# IO__MCP23017_20240819.net
KiCad netlist of a schematic drawn in Altium Designer
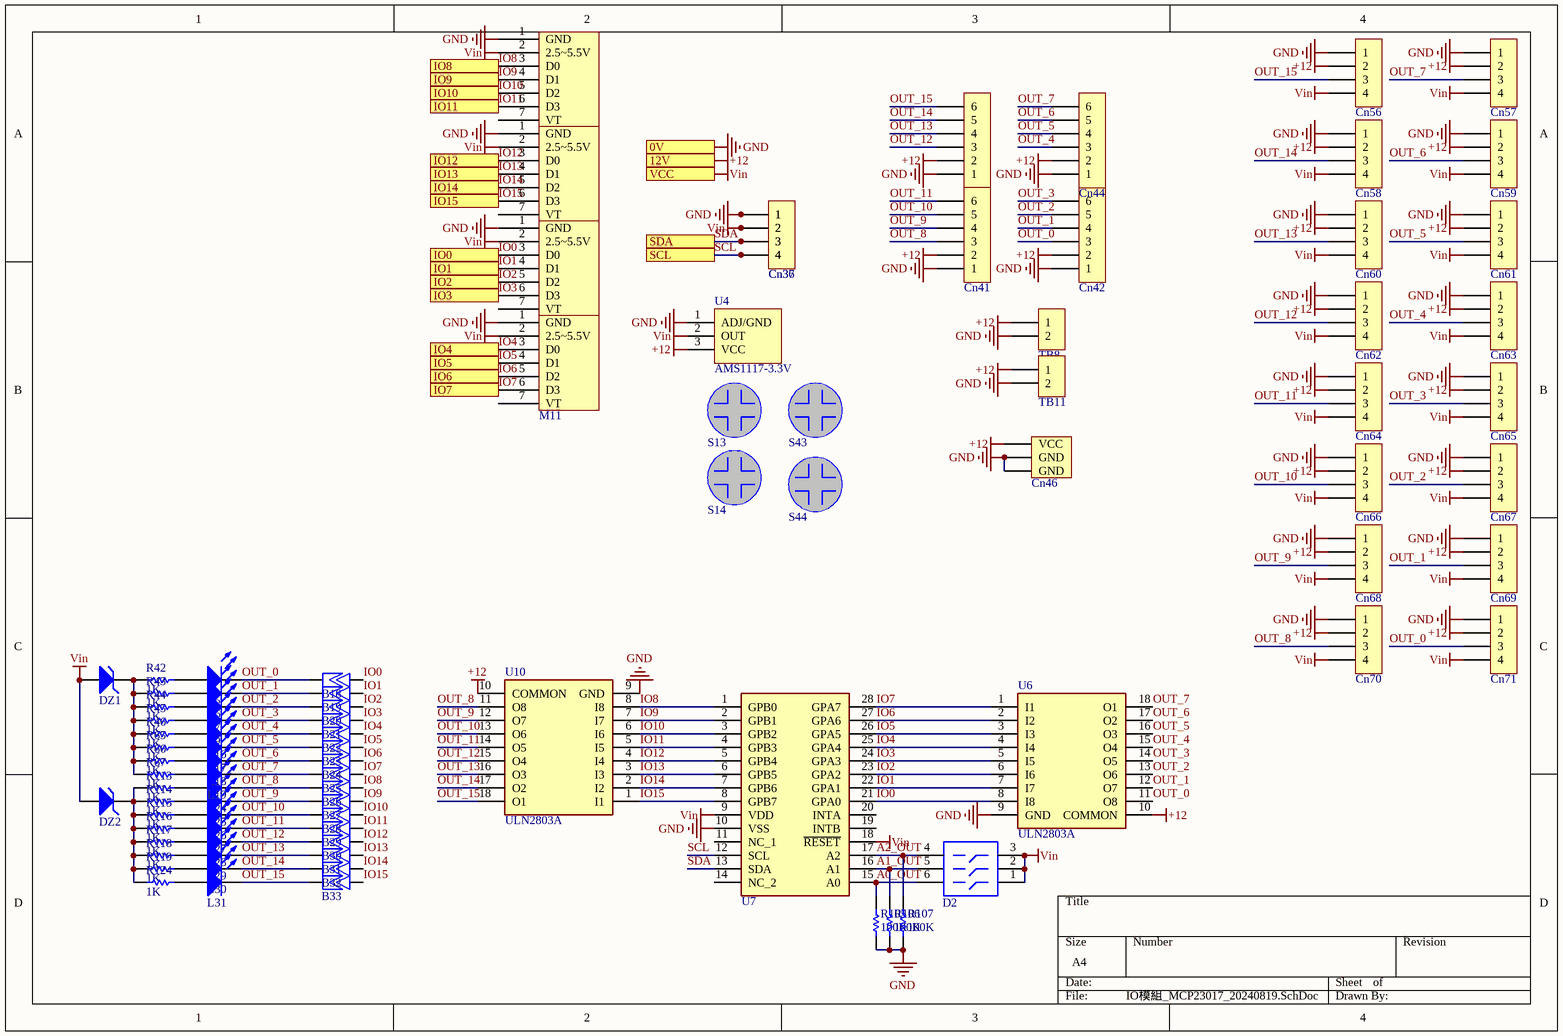
[diagram p0: IO模組_MCP23017_20240819.SchDoc]

(export (version "E")
  (design (tool "Eeschema 10.0.6"))
  (components
    (comp (ref "B18")
      (value "短路")
      (footprint "BYPASS-0805")
      (description "短路焊點(如標註短路則需額外補錫使其短路)")
      (libsource (lib "MyLibray") (part "Bypass"))
    )
    (comp (ref "B19")
      (value "短路")
      (footprint "BYPASS-0805")
      (description "短路焊點(如標註短路則需額外補錫使其短路)")
      (libsource (lib "MyLibray") (part "Bypass"))
    )
    (comp (ref "B20")
      (value "短路")
      (footprint "BYPASS-0805")
      (description "短路焊點(如標註短路則需額外補錫使其短路)")
      (libsource (lib "MyLibray") (part "Bypass"))
    )
    (comp (ref "B21")
      (value "短路")
      (footprint "BYPASS-0805")
      (description "短路焊點(如標註短路則需額外補錫使其短路)")
      (libsource (lib "MyLibray") (part "Bypass"))
    )
    (comp (ref "B22")
      (value "短路")
      (footprint "BYPASS-0805")
      (description "短路焊點(如標註短路則需額外補錫使其短路)")
      (libsource (lib "MyLibray") (part "Bypass"))
    )
    (comp (ref "B23")
      (value "短路")
      (footprint "BYPASS-0805")
      (description "短路焊點(如標註短路則需額外補錫使其短路)")
      (libsource (lib "MyLibray") (part "Bypass"))
    )
    (comp (ref "B24")
      (value "短路")
      (footprint "BYPASS-0805")
      (description "短路焊點(如標註短路則需額外補錫使其短路)")
      (libsource (lib "MyLibray") (part "Bypass"))
    )
    (comp (ref "B25")
      (value "短路")
      (footprint "BYPASS-0805")
      (description "短路焊點(如標註短路則需額外補錫使其短路)")
      (libsource (lib "MyLibray") (part "Bypass"))
    )
    (comp (ref "B26")
      (value "短路")
      (footprint "BYPASS-0805")
      (description "短路焊點(如標註短路則需額外補錫使其短路)")
      (libsource (lib "MyLibray") (part "Bypass"))
    )
    (comp (ref "B27")
      (value "短路")
      (footprint "BYPASS-0805")
      (description "短路焊點(如標註短路則需額外補錫使其短路)")
      (libsource (lib "MyLibray") (part "Bypass"))
    )
    (comp (ref "B28")
      (value "短路")
      (footprint "BYPASS-0805")
      (description "短路焊點(如標註短路則需額外補錫使其短路)")
      (libsource (lib "MyLibray") (part "Bypass"))
    )
    (comp (ref "B29")
      (value "短路")
      (footprint "BYPASS-0805")
      (description "短路焊點(如標註短路則需額外補錫使其短路)")
      (libsource (lib "MyLibray") (part "Bypass"))
    )
    (comp (ref "B30")
      (value "短路")
      (footprint "BYPASS-0805")
      (description "短路焊點(如標註短路則需額外補錫使其短路)")
      (libsource (lib "MyLibray") (part "Bypass"))
    )
    (comp (ref "B31")
      (value "短路")
      (footprint "BYPASS-0805")
      (description "短路焊點(如標註短路則需額外補錫使其短路)")
      (libsource (lib "MyLibray") (part "Bypass"))
    )
    (comp (ref "B32")
      (value "短路")
      (footprint "BYPASS-0805")
      (description "短路焊點(如標註短路則需額外補錫使其短路)")
      (libsource (lib "MyLibray") (part "Bypass"))
    )
    (comp (ref "B33")
      (value "短路")
      (footprint "BYPASS-0805")
      (description "短路焊點(如標註短路則需額外補錫使其短路)")
      (libsource (lib "MyLibray") (part "Bypass"))
    )
    (comp (ref "Cn36")
      (value "KF2510")
      (footprint "Connector_KF2510-4A")
      (description "接線端子")
      (libsource (lib "MyLibray") (part "Contact(4P)"))
    )
    (comp (ref "Cn37")
      (value "KF2510")
      (footprint "Connector_KF2510-4A")
      (description "接線端子")
      (libsource (lib "MyLibray") (part "Contact(4P)"))
    )
    (comp (ref "Cn39")
      (value "KF2510-6")
      (footprint "Connector_KF2510-6W")
      (description "接線端子")
      (libsource (lib "MyLibray") (part "Contact(6P)"))
    )
    (comp (ref "Cn41")
      (value "KF2510-6")
      (footprint "Connector_KF2510-6W")
      (description "接線端子")
      (libsource (lib "MyLibray") (part "Contact(6P)"))
    )
    (comp (ref "Cn42")
      (value "KF2510-6")
      (footprint "Connector_KF2510-6W")
      (description "接線端子")
      (libsource (lib "MyLibray") (part "Contact(6P)"))
    )
    (comp (ref "Cn44")
      (value "KF2510-6")
      (footprint "Connector_KF2510-6W")
      (description "接線端子")
      (libsource (lib "MyLibray") (part "Contact(6P)"))
    )
    (comp (ref "Cn46")
      (value "KF2510-4")
      (footprint "Connector_DC-005")
      (description "接線端子")
      (libsource (lib "MyLibray") (part "Contact_DC"))
    )
    (comp (ref "Cn56")
      (value "KF2510")
      (footprint "Connector_KF2510-4A")
      (description "接線端子")
      (libsource (lib "MyLibray") (part "Contact(4P)"))
    )
    (comp (ref "Cn57")
      (value "KF2510")
      (footprint "Connector_KF2510-4A")
      (description "接線端子")
      (libsource (lib "MyLibray") (part "Contact(4P)"))
    )
    (comp (ref "Cn58")
      (value "KF2510")
      (footprint "Connector_KF2510-4A")
      (description "接線端子")
      (libsource (lib "MyLibray") (part "Contact(4P)"))
    )
    (comp (ref "Cn59")
      (value "KF2510")
      (footprint "Connector_KF2510-4A")
      (description "接線端子")
      (libsource (lib "MyLibray") (part "Contact(4P)"))
    )
    (comp (ref "Cn60")
      (value "KF2510")
      (footprint "Connector_KF2510-4A")
      (description "接線端子")
      (libsource (lib "MyLibray") (part "Contact(4P)"))
    )
    (comp (ref "Cn61")
      (value "KF2510")
      (footprint "Connector_KF2510-4A")
      (description "接線端子")
      (libsource (lib "MyLibray") (part "Contact(4P)"))
    )
    (comp (ref "Cn62")
      (value "KF2510")
      (footprint "Connector_KF2510-4A")
      (description "接線端子")
      (libsource (lib "MyLibray") (part "Contact(4P)"))
    )
    (comp (ref "Cn63")
      (value "KF2510")
      (footprint "Connector_KF2510-4A")
      (description "接線端子")
      (libsource (lib "MyLibray") (part "Contact(4P)"))
    )
    (comp (ref "Cn64")
      (value "KF2510")
      (footprint "Connector_KF2510-4A")
      (description "接線端子")
      (libsource (lib "MyLibray") (part "Contact(4P)"))
    )
    (comp (ref "Cn65")
      (value "KF2510")
      (footprint "Connector_KF2510-4A")
      (description "接線端子")
      (libsource (lib "MyLibray") (part "Contact(4P)"))
    )
    (comp (ref "Cn66")
      (value "KF2510")
      (footprint "Connector_KF2510-4A")
      (description "接線端子")
      (libsource (lib "MyLibray") (part "Contact(4P)"))
    )
    (comp (ref "Cn67")
      (value "KF2510")
      (footprint "Connector_KF2510-4A")
      (description "接線端子")
      (libsource (lib "MyLibray") (part "Contact(4P)"))
    )
    (comp (ref "Cn68")
      (value "KF2510")
      (footprint "Connector_KF2510-4A")
      (description "接線端子")
      (libsource (lib "MyLibray") (part "Contact(4P)"))
    )
    (comp (ref "Cn69")
      (value "KF2510")
      (footprint "Connector_KF2510-4A")
      (description "接線端子")
      (libsource (lib "MyLibray") (part "Contact(4P)"))
    )
    (comp (ref "Cn70")
      (value "KF2510")
      (footprint "Connector_KF2510-4A")
      (description "接線端子")
      (libsource (lib "MyLibray") (part "Contact(4P)"))
    )
    (comp (ref "Cn71")
      (value "KF2510")
      (footprint "Connector_KF2510-4A")
      (description "接線端子")
      (libsource (lib "MyLibray") (part "Contact(4P)"))
    )
    (comp (ref "D2")
      (value "KE 撥碼開關 1.27mm")
      (footprint "Switch_Dip-3")
      (description "開關_撥碼_3位")
      (libsource (lib "MyLibray") (part "Switch_Dip _3"))
    )
    (comp (ref "DZ1")
      (value "12V1")
      (footprint "Diode_1/4")
      (description "二極體_稽納")
      (libsource (lib "MyLibray") (part "Diode_Zener"))
    )
    (comp (ref "DZ2")
      (value "12V1")
      (footprint "Diode_1/4")
      (description "二極體_稽納")
      (libsource (lib "MyLibray") (part "Diode_Zener"))
    )
    (comp (ref "L5")
      (value "藍")
      (footprint "LED-1206")
      (description "LED")
      (libsource (lib "MyLibray") (part "LED"))
    )
    (comp (ref "L6")
      (value "藍")
      (footprint "LED-1206")
      (description "LED")
      (libsource (lib "MyLibray") (part "LED"))
    )
    (comp (ref "L7")
      (value "藍")
      (footprint "LED-1206")
      (description "LED")
      (libsource (lib "MyLibray") (part "LED"))
    )
    (comp (ref "L9")
      (value "藍")
      (footprint "LED-1206")
      (description "LED")
      (libsource (lib "MyLibray") (part "LED"))
    )
    (comp (ref "L16")
      (value "藍")
      (footprint "LED-1206")
      (description "LED")
      (libsource (lib "MyLibray") (part "LED"))
    )
    (comp (ref "L17")
      (value "藍")
      (footprint "LED-1206")
      (description "LED")
      (libsource (lib "MyLibray") (part "LED"))
    )
    (comp (ref "L18")
      (value "藍")
      (footprint "LED-1206")
      (description "LED")
      (libsource (lib "MyLibray") (part "LED"))
    )
    (comp (ref "L19")
      (value "藍")
      (footprint "LED-1206")
      (description "LED")
      (libsource (lib "MyLibray") (part "LED"))
    )
    (comp (ref "L24")
      (value "藍")
      (footprint "LED-1206")
      (description "LED")
      (libsource (lib "MyLibray") (part "LED"))
    )
    (comp (ref "L25")
      (value "藍")
      (footprint "LED-1206")
      (description "LED")
      (libsource (lib "MyLibray") (part "LED"))
    )
    (comp (ref "L26")
      (value "藍")
      (footprint "LED-1206")
      (description "LED")
      (libsource (lib "MyLibray") (part "LED"))
    )
    (comp (ref "L27")
      (value "藍")
      (footprint "LED-1206")
      (description "LED")
      (libsource (lib "MyLibray") (part "LED"))
    )
    (comp (ref "L28")
      (value "藍")
      (footprint "LED-1206")
      (description "LED")
      (libsource (lib "MyLibray") (part "LED"))
    )
    (comp (ref "L29")
      (value "藍")
      (footprint "LED-1206")
      (description "LED")
      (libsource (lib "MyLibray") (part "LED"))
    )
    (comp (ref "L30")
      (value "藍")
      (footprint "LED-1206")
      (description "LED")
      (libsource (lib "MyLibray") (part "LED"))
    )
    (comp (ref "L31")
      (value "藍")
      (footprint "LED-1206")
      (description "LED")
      (libsource (lib "MyLibray") (part "LED"))
    )
    (comp (ref "M8")
      (value "XR390")
      (footprint "XR390 Module")
      (description "遙控器模組")
      (libsource (lib "MyModule") (part "XR390"))
    )
    (comp (ref "M9")
      (value "XR390")
      (footprint "XR390 Module")
      (description "遙控器模組")
      (libsource (lib "MyModule") (part "XR390"))
    )
    (comp (ref "M10")
      (value "XR390")
      (footprint "XR390 Module")
      (description "遙控器模組")
      (libsource (lib "MyModule") (part "XR390"))
    )
    (comp (ref "M11")
      (value "XR390")
      (footprint "XR390 Module")
      (description "遙控器模組")
      (libsource (lib "MyModule") (part "XR390"))
    )
    (comp (ref "R42")
      (value "1K")
      (footprint "Res-1206")
      (description "電阻")
      (libsource (lib "MyLibray") (part "Res"))
    )
    (comp (ref "R43")
      (value "1K")
      (footprint "Res-1206")
      (description "電阻")
      (libsource (lib "MyLibray") (part "Res"))
    )
    (comp (ref "R44")
      (value "1K")
      (footprint "Res-1206")
      (description "電阻")
      (libsource (lib "MyLibray") (part "Res"))
    )
    (comp (ref "R45")
      (value "1K")
      (footprint "Res-1206")
      (description "電阻")
      (libsource (lib "MyLibray") (part "Res"))
    )
    (comp (ref "R46")
      (value "1K")
      (footprint "Res-1206")
      (description "電阻")
      (libsource (lib "MyLibray") (part "Res"))
    )
    (comp (ref "R65")
      (value "1K")
      (footprint "Res-1206")
      (description "電阻")
      (libsource (lib "MyLibray") (part "Res"))
    )
    (comp (ref "R66")
      (value "1K")
      (footprint "Res-1206")
      (description "電阻")
      (libsource (lib "MyLibray") (part "Res"))
    )
    (comp (ref "R67")
      (value "1K")
      (footprint "Res-1206")
      (description "電阻")
      (libsource (lib "MyLibray") (part "Res"))
    )
    (comp (ref "R105")
      (value "100K")
      (footprint "Res-1206")
      (description "電阻")
      (libsource (lib "MyLibray") (part "Res"))
    )
    (comp (ref "R106")
      (value "100K")
      (footprint "Res-1206")
      (description "電阻")
      (libsource (lib "MyLibray") (part "Res"))
    )
    (comp (ref "R107")
      (value "100K")
      (footprint "Res-1206")
      (description "電阻")
      (libsource (lib "MyLibray") (part "Res"))
    )
    (comp (ref "R113")
      (value "1K")
      (footprint "Res-1206")
      (description "電阻")
      (libsource (lib "MyLibray") (part "Res"))
    )
    (comp (ref "R114")
      (value "1K")
      (footprint "Res-1206")
      (description "電阻")
      (libsource (lib "MyLibray") (part "Res"))
    )
    (comp (ref "R115")
      (value "1K")
      (footprint "Res-1206")
      (description "電阻")
      (libsource (lib "MyLibray") (part "Res"))
    )
    (comp (ref "R116")
      (value "1K")
      (footprint "Res-1206")
      (description "電阻")
      (libsource (lib "MyLibray") (part "Res"))
    )
    (comp (ref "R117")
      (value "1K")
      (footprint "Res-1206")
      (description "電阻")
      (libsource (lib "MyLibray") (part "Res"))
    )
    (comp (ref "R118")
      (value "1K")
      (footprint "Res-1206")
      (description "電阻")
      (libsource (lib "MyLibray") (part "Res"))
    )
    (comp (ref "R119")
      (value "1K")
      (footprint "Res-1206")
      (description "電阻")
      (libsource (lib "MyLibray") (part "Res"))
    )
    (comp (ref "R124")
      (value "1K")
      (footprint "Res-1206")
      (description "電阻")
      (libsource (lib "MyLibray") (part "Res"))
    )
    (comp (ref "S13")
      (value "M3")
      (footprint "Screw M3")
      (description "螺絲(非焊接元件)")
      (libsource (lib "MyLibray") (part "Screw"))
    )
    (comp (ref "S14")
      (value "M3")
      (footprint "Screw M3")
      (description "螺絲(非焊接元件)")
      (libsource (lib "MyLibray") (part "Screw"))
    )
    (comp (ref "S43")
      (value "M3")
      (footprint "Screw M3")
      (description "螺絲(非焊接元件)")
      (libsource (lib "MyLibray") (part "Screw"))
    )
    (comp (ref "S44")
      (value "M3")
      (footprint "Screw M3")
      (description "螺絲(非焊接元件)")
      (libsource (lib "MyLibray") (part "Screw"))
    )
    (comp (ref "TB8")
      (value "KF2EDG5.08_2P")
      (footprint "Terminal block(KF2EDGR-5.08 _2P)")
      (description "端子台")
      (libsource (lib "MyLibray") (part "Terminal block(2P)"))
    )
    (comp (ref "TB11")
      (value "KF2EDG5.08_2P")
      (footprint "Terminal block(KF2EDGR-5.08 _2P)")
      (description "端子台")
      (libsource (lib "MyLibray") (part "Terminal block(2P)"))
    )
    (comp (ref "U4")
      (value "AMS1117-3.3V")
      (footprint "SOT 223")
      (description "降壓IC,LOD")
      (libsource (lib "MyLibray") (part "AMS1117"))
    )
    (comp (ref "U6")
      (value "ULN2803A")
      (footprint "DIP-18")
      (description "閘極驅動器 P型 50V 0.5A")
      (fields
        (field (name "MOUSER PART NUMBER") "757-TBD60183AFNGEL")
        (field (name "MANUFACTURER_PART_NUMBER") "TBD62083AFNG,EL")
      )
      (libsource (lib "") (part "TBD62083A_1"))
    )
    (comp (ref "U7")
      (value "MCP23017")
      (footprint "DIP-28")
      (description "I2C IO")
      (fields (field (name "MANUFACTURER_PART_NUMBER") "MCP23017-E/SO"))
      (libsource (lib "MyLibray") (part "MCP23017"))
    )
    (comp (ref "U10")
      (value "ULN2803A")
      (footprint "DIP-18")
      (description "閘極驅動器 P型 50V 0.5A")
      (fields
        (field (name "MOUSER PART NUMBER") "757-TBD60183AFNGEL")
        (field (name "MANUFACTURER_PART_NUMBER") "TBD62083AFNG,EL")
      )
      (libsource (lib "MyLibray") (part "TBD62083A"))
    )
  )
  (nets
    (net (code "1") (name "+12") (class "Default")
      (node (ref "Cn39") (pin "2") (pinfunction "2_2") (pintype "passive"))
      (node (ref "Cn41") (pin "2") (pinfunction "2_2") (pintype "passive"))
      (node (ref "Cn42") (pin "2") (pinfunction "2_2") (pintype "passive"))
      (node (ref "Cn44") (pin "2") (pinfunction "2_2") (pintype "passive"))
      (node (ref "Cn46") (pin "1") (pinfunction "VCC_1") (pintype "passive"))
      (node (ref "Cn56") (pin "2") (pinfunction "2_2") (pintype "passive"))
      (node (ref "Cn57") (pin "2") (pinfunction "2_2") (pintype "passive"))
      (node (ref "Cn58") (pin "2") (pinfunction "2_2") (pintype "passive"))
      (node (ref "Cn59") (pin "2") (pinfunction "2_2") (pintype "passive"))
      (node (ref "Cn60") (pin "2") (pinfunction "2_2") (pintype "passive"))
      (node (ref "Cn61") (pin "2") (pinfunction "2_2") (pintype "passive"))
      (node (ref "Cn62") (pin "2") (pinfunction "2_2") (pintype "passive"))
      (node (ref "Cn63") (pin "2") (pinfunction "2_2") (pintype "passive"))
      (node (ref "Cn64") (pin "2") (pinfunction "2_2") (pintype "passive"))
      (node (ref "Cn65") (pin "2") (pinfunction "2_2") (pintype "passive"))
      (node (ref "Cn66") (pin "2") (pinfunction "2_2") (pintype "passive"))
      (node (ref "Cn67") (pin "2") (pinfunction "2_2") (pintype "passive"))
      (node (ref "Cn68") (pin "2") (pinfunction "2_2") (pintype "passive"))
      (node (ref "Cn69") (pin "2") (pinfunction "2_2") (pintype "passive"))
      (node (ref "Cn70") (pin "2") (pinfunction "2_2") (pintype "passive"))
      (node (ref "Cn71") (pin "2") (pinfunction "2_2") (pintype "passive"))
      (node (ref "TB11") (pin "1") (pinfunction "1_1") (pintype "passive"))
      (node (ref "TB8") (pin "1") (pinfunction "1_1") (pintype "passive"))
      (node (ref "U10") (pin "10") (pinfunction "COMMON_10") (pintype "passive"))
      (node (ref "U4") (pin "3") (pinfunction "VCC_3") (pintype "power_in"))
      (node (ref "U6") (pin "10") (pinfunction "COMMON_10") (pintype "passive"))
    )
    (net (code "2") (name "/A0_OUT") (class "Default")
      (node (ref "D2") (pin "6") (pinfunction "6_6") (pintype "passive"))
      (node (ref "R105") (pin "2") (pinfunction "2_2") (pintype "passive"))
      (node (ref "U7") (pin "15") (pinfunction "A0_15") (pintype "passive"))
    )
    (net (code "3") (name "/A1_OUT") (class "Default")
      (node (ref "D2") (pin "5") (pinfunction "5_5") (pintype "passive"))
      (node (ref "R106") (pin "2") (pinfunction "2_2") (pintype "passive"))
      (node (ref "U7") (pin "16") (pinfunction "A1_16") (pintype "passive"))
    )
    (net (code "4") (name "/A2_OUT") (class "Default")
      (node (ref "D2") (pin "4") (pinfunction "4_4") (pintype "passive"))
      (node (ref "R107") (pin "2") (pinfunction "2_2") (pintype "passive"))
      (node (ref "U7") (pin "17") (pinfunction "A2_17") (pintype "passive"))
    )
    (net (code "5") (name "/IO0") (class "Default")
      (node (ref "B18") (pin "2") (pinfunction "2_2") (pintype "passive"))
      (node (ref "M10") (pin "3") (pinfunction "D0_3") (pintype "passive"))
      (node (ref "U6") (pin "8") (pinfunction "I8_8") (pintype "passive"))
      (node (ref "U7") (pin "21") (pinfunction "GPA0_21") (pintype "passive"))
    )
    (net (code "6") (name "/IO1") (class "Default")
      (node (ref "B19") (pin "2") (pinfunction "2_2") (pintype "passive"))
      (node (ref "M10") (pin "4") (pinfunction "D1_4") (pintype "passive"))
      (node (ref "U6") (pin "7") (pinfunction "I7_7") (pintype "passive"))
      (node (ref "U7") (pin "22") (pinfunction "GPA1_22") (pintype "passive"))
    )
    (net (code "7") (name "/IO2") (class "Default")
      (node (ref "B20") (pin "2") (pinfunction "2_2") (pintype "passive"))
      (node (ref "M10") (pin "5") (pinfunction "D2_5") (pintype "passive"))
      (node (ref "U6") (pin "6") (pinfunction "I6_6") (pintype "passive"))
      (node (ref "U7") (pin "23") (pinfunction "GPA2_23") (pintype "passive"))
    )
    (net (code "8") (name "/IO3") (class "Default")
      (node (ref "B21") (pin "2") (pinfunction "2_2") (pintype "passive"))
      (node (ref "M10") (pin "6") (pinfunction "D3_6") (pintype "passive"))
      (node (ref "U6") (pin "5") (pinfunction "I5_5") (pintype "passive"))
      (node (ref "U7") (pin "24") (pinfunction "GPA3_24") (pintype "passive"))
    )
    (net (code "9") (name "/IO4") (class "Default")
      (node (ref "B22") (pin "2") (pinfunction "2_2") (pintype "passive"))
      (node (ref "M11") (pin "3") (pinfunction "D0_3") (pintype "passive"))
      (node (ref "U6") (pin "4") (pinfunction "I4_4") (pintype "passive"))
      (node (ref "U7") (pin "25") (pinfunction "GPA4_25") (pintype "passive"))
    )
    (net (code "10") (name "/IO5") (class "Default")
      (node (ref "B23") (pin "2") (pinfunction "2_2") (pintype "passive"))
      (node (ref "M11") (pin "4") (pinfunction "D1_4") (pintype "passive"))
      (node (ref "U6") (pin "3") (pinfunction "I3_3") (pintype "passive"))
      (node (ref "U7") (pin "26") (pinfunction "GPA5_26") (pintype "passive"))
    )
    (net (code "11") (name "/IO6") (class "Default")
      (node (ref "B24") (pin "2") (pinfunction "2_2") (pintype "passive"))
      (node (ref "M11") (pin "5") (pinfunction "D2_5") (pintype "passive"))
      (node (ref "U6") (pin "2") (pinfunction "I2_2") (pintype "passive"))
      (node (ref "U7") (pin "27") (pinfunction "GPA6_27") (pintype "passive"))
    )
    (net (code "12") (name "/IO7") (class "Default")
      (node (ref "B25") (pin "2") (pinfunction "2_2") (pintype "passive"))
      (node (ref "M11") (pin "6") (pinfunction "D3_6") (pintype "passive"))
      (node (ref "U6") (pin "1") (pinfunction "I1_1") (pintype "passive"))
      (node (ref "U7") (pin "28") (pinfunction "GPA7_28") (pintype "passive"))
    )
    (net (code "13") (name "/IO8") (class "Default")
      (node (ref "B26") (pin "2") (pinfunction "2_2") (pintype "passive"))
      (node (ref "M8") (pin "3") (pinfunction "D0_3") (pintype "passive"))
      (node (ref "U10") (pin "8") (pinfunction "I8_8") (pintype "passive"))
      (node (ref "U7") (pin "1") (pinfunction "GPB0_1") (pintype "passive"))
    )
    (net (code "14") (name "/IO9") (class "Default")
      (node (ref "B27") (pin "2") (pinfunction "2_2") (pintype "passive"))
      (node (ref "M8") (pin "4") (pinfunction "D1_4") (pintype "passive"))
      (node (ref "U10") (pin "7") (pinfunction "I7_7") (pintype "passive"))
      (node (ref "U7") (pin "2") (pinfunction "GPB1_2") (pintype "passive"))
    )
    (net (code "15") (name "/IO10") (class "Default")
      (node (ref "B28") (pin "2") (pinfunction "2_2") (pintype "passive"))
      (node (ref "M8") (pin "5") (pinfunction "D2_5") (pintype "passive"))
      (node (ref "U10") (pin "6") (pinfunction "I6_6") (pintype "passive"))
      (node (ref "U7") (pin "3") (pinfunction "GPB2_3") (pintype "passive"))
    )
    (net (code "16") (name "/IO11") (class "Default")
      (node (ref "B29") (pin "2") (pinfunction "2_2") (pintype "passive"))
      (node (ref "M8") (pin "6") (pinfunction "D3_6") (pintype "passive"))
      (node (ref "U10") (pin "5") (pinfunction "I5_5") (pintype "passive"))
      (node (ref "U7") (pin "4") (pinfunction "GPB3_4") (pintype "passive"))
    )
    (net (code "17") (name "/IO12") (class "Default")
      (node (ref "B30") (pin "2") (pinfunction "2_2") (pintype "passive"))
      (node (ref "M9") (pin "3") (pinfunction "D0_3") (pintype "passive"))
      (node (ref "U10") (pin "4") (pinfunction "I4_4") (pintype "passive"))
      (node (ref "U7") (pin "5") (pinfunction "GPB4_5") (pintype "passive"))
    )
    (net (code "18") (name "/IO13") (class "Default")
      (node (ref "B31") (pin "2") (pinfunction "2_2") (pintype "passive"))
      (node (ref "M9") (pin "4") (pinfunction "D1_4") (pintype "passive"))
      (node (ref "U10") (pin "3") (pinfunction "I3_3") (pintype "passive"))
      (node (ref "U7") (pin "6") (pinfunction "GPB5_6") (pintype "passive"))
    )
    (net (code "19") (name "/IO14") (class "Default")
      (node (ref "B32") (pin "2") (pinfunction "2_2") (pintype "passive"))
      (node (ref "M9") (pin "5") (pinfunction "D2_5") (pintype "passive"))
      (node (ref "U10") (pin "2") (pinfunction "I2_2") (pintype "passive"))
      (node (ref "U7") (pin "7") (pinfunction "GPB6_7") (pintype "passive"))
    )
    (net (code "20") (name "/IO15") (class "Default")
      (node (ref "B33") (pin "2") (pinfunction "2_2") (pintype "passive"))
      (node (ref "M9") (pin "6") (pinfunction "D3_6") (pintype "passive"))
      (node (ref "U10") (pin "1") (pinfunction "I1_1") (pintype "passive"))
      (node (ref "U7") (pin "8") (pinfunction "GPB7_8") (pintype "passive"))
    )
    (net (code "21") (name "/OUT_0") (class "Default")
      (node (ref "B18") (pin "1") (pinfunction "1_1") (pintype "passive"))
      (node (ref "Cn42") (pin "3") (pinfunction "3_3") (pintype "passive"))
      (node (ref "Cn71") (pin "3") (pinfunction "3_3") (pintype "passive"))
      (node (ref "L5") (pin "1") (pinfunction "K_1") (pintype "passive"))
      (node (ref "U6") (pin "11") (pinfunction "O8_11") (pintype "passive"))
    )
    (net (code "22") (name "/OUT_1") (class "Default")
      (node (ref "B19") (pin "1") (pinfunction "1_1") (pintype "passive"))
      (node (ref "Cn42") (pin "4") (pinfunction "4_4") (pintype "passive"))
      (node (ref "Cn69") (pin "3") (pinfunction "3_3") (pintype "passive"))
      (node (ref "L6") (pin "1") (pinfunction "K_1") (pintype "passive"))
      (node (ref "U6") (pin "12") (pinfunction "O7_12") (pintype "passive"))
    )
    (net (code "23") (name "/OUT_2") (class "Default")
      (node (ref "B20") (pin "1") (pinfunction "1_1") (pintype "passive"))
      (node (ref "Cn42") (pin "5") (pinfunction "5_5") (pintype "passive"))
      (node (ref "Cn67") (pin "3") (pinfunction "3_3") (pintype "passive"))
      (node (ref "L7") (pin "1") (pinfunction "K_1") (pintype "passive"))
      (node (ref "U6") (pin "13") (pinfunction "O6_13") (pintype "passive"))
    )
    (net (code "24") (name "/OUT_3") (class "Default")
      (node (ref "B21") (pin "1") (pinfunction "1_1") (pintype "passive"))
      (node (ref "Cn42") (pin "6") (pinfunction "6_6") (pintype "passive"))
      (node (ref "Cn65") (pin "3") (pinfunction "3_3") (pintype "passive"))
      (node (ref "L9") (pin "1") (pinfunction "K_1") (pintype "passive"))
      (node (ref "U6") (pin "14") (pinfunction "O5_14") (pintype "passive"))
    )
    (net (code "25") (name "/OUT_4") (class "Default")
      (node (ref "B22") (pin "1") (pinfunction "1_1") (pintype "passive"))
      (node (ref "Cn44") (pin "3") (pinfunction "3_3") (pintype "passive"))
      (node (ref "Cn63") (pin "3") (pinfunction "3_3") (pintype "passive"))
      (node (ref "L16") (pin "1") (pinfunction "K_1") (pintype "passive"))
      (node (ref "U6") (pin "15") (pinfunction "O4_15") (pintype "passive"))
    )
    (net (code "26") (name "/OUT_5") (class "Default")
      (node (ref "B23") (pin "1") (pinfunction "1_1") (pintype "passive"))
      (node (ref "Cn44") (pin "4") (pinfunction "4_4") (pintype "passive"))
      (node (ref "Cn61") (pin "3") (pinfunction "3_3") (pintype "passive"))
      (node (ref "L17") (pin "1") (pinfunction "K_1") (pintype "passive"))
      (node (ref "U6") (pin "16") (pinfunction "O3_16") (pintype "passive"))
    )
    (net (code "27") (name "/OUT_6") (class "Default")
      (node (ref "B24") (pin "1") (pinfunction "1_1") (pintype "passive"))
      (node (ref "Cn44") (pin "5") (pinfunction "5_5") (pintype "passive"))
      (node (ref "Cn59") (pin "3") (pinfunction "3_3") (pintype "passive"))
      (node (ref "L18") (pin "1") (pinfunction "K_1") (pintype "passive"))
      (node (ref "U6") (pin "17") (pinfunction "O2_17") (pintype "passive"))
    )
    (net (code "28") (name "/OUT_7") (class "Default")
      (node (ref "B25") (pin "1") (pinfunction "1_1") (pintype "passive"))
      (node (ref "Cn44") (pin "6") (pinfunction "6_6") (pintype "passive"))
      (node (ref "Cn57") (pin "3") (pinfunction "3_3") (pintype "passive"))
      (node (ref "L19") (pin "1") (pinfunction "K_1") (pintype "passive"))
      (node (ref "U6") (pin "18") (pinfunction "O1_18") (pintype "passive"))
    )
    (net (code "29") (name "/OUT_8") (class "Default")
      (node (ref "B26") (pin "1") (pinfunction "1_1") (pintype "passive"))
      (node (ref "Cn41") (pin "3") (pinfunction "3_3") (pintype "passive"))
      (node (ref "Cn70") (pin "3") (pinfunction "3_3") (pintype "passive"))
      (node (ref "L24") (pin "1") (pinfunction "K_1") (pintype "passive"))
      (node (ref "U10") (pin "11") (pinfunction "O8_11") (pintype "passive"))
    )
    (net (code "30") (name "/OUT_9") (class "Default")
      (node (ref "B27") (pin "1") (pinfunction "1_1") (pintype "passive"))
      (node (ref "Cn41") (pin "4") (pinfunction "4_4") (pintype "passive"))
      (node (ref "Cn68") (pin "3") (pinfunction "3_3") (pintype "passive"))
      (node (ref "L25") (pin "1") (pinfunction "K_1") (pintype "passive"))
      (node (ref "U10") (pin "12") (pinfunction "O7_12") (pintype "passive"))
    )
    (net (code "31") (name "/OUT_10") (class "Default")
      (node (ref "B28") (pin "1") (pinfunction "1_1") (pintype "passive"))
      (node (ref "Cn41") (pin "5") (pinfunction "5_5") (pintype "passive"))
      (node (ref "Cn66") (pin "3") (pinfunction "3_3") (pintype "passive"))
      (node (ref "L26") (pin "1") (pinfunction "K_1") (pintype "passive"))
      (node (ref "U10") (pin "13") (pinfunction "O6_13") (pintype "passive"))
    )
    (net (code "32") (name "/OUT_11") (class "Default")
      (node (ref "B29") (pin "1") (pinfunction "1_1") (pintype "passive"))
      (node (ref "Cn41") (pin "6") (pinfunction "6_6") (pintype "passive"))
      (node (ref "Cn64") (pin "3") (pinfunction "3_3") (pintype "passive"))
      (node (ref "L27") (pin "1") (pinfunction "K_1") (pintype "passive"))
      (node (ref "U10") (pin "14") (pinfunction "O5_14") (pintype "passive"))
    )
    (net (code "33") (name "/OUT_12") (class "Default")
      (node (ref "B30") (pin "1") (pinfunction "1_1") (pintype "passive"))
      (node (ref "Cn39") (pin "3") (pinfunction "3_3") (pintype "passive"))
      (node (ref "Cn62") (pin "3") (pinfunction "3_3") (pintype "passive"))
      (node (ref "L28") (pin "1") (pinfunction "K_1") (pintype "passive"))
      (node (ref "U10") (pin "15") (pinfunction "O4_15") (pintype "passive"))
    )
    (net (code "34") (name "/OUT_13") (class "Default")
      (node (ref "B31") (pin "1") (pinfunction "1_1") (pintype "passive"))
      (node (ref "Cn39") (pin "4") (pinfunction "4_4") (pintype "passive"))
      (node (ref "Cn60") (pin "3") (pinfunction "3_3") (pintype "passive"))
      (node (ref "L29") (pin "1") (pinfunction "K_1") (pintype "passive"))
      (node (ref "U10") (pin "16") (pinfunction "O3_16") (pintype "passive"))
    )
    (net (code "35") (name "/OUT_14") (class "Default")
      (node (ref "B32") (pin "1") (pinfunction "1_1") (pintype "passive"))
      (node (ref "Cn39") (pin "5") (pinfunction "5_5") (pintype "passive"))
      (node (ref "Cn58") (pin "3") (pinfunction "3_3") (pintype "passive"))
      (node (ref "L30") (pin "1") (pinfunction "K_1") (pintype "passive"))
      (node (ref "U10") (pin "17") (pinfunction "O2_17") (pintype "passive"))
    )
    (net (code "36") (name "/OUT_15") (class "Default")
      (node (ref "B33") (pin "1") (pinfunction "1_1") (pintype "passive"))
      (node (ref "Cn39") (pin "6") (pinfunction "6_6") (pintype "passive"))
      (node (ref "Cn56") (pin "3") (pinfunction "3_3") (pintype "passive"))
      (node (ref "L31") (pin "1") (pinfunction "K_1") (pintype "passive"))
      (node (ref "U10") (pin "18") (pinfunction "O1_18") (pintype "passive"))
    )
    (net (code "37") (name "/SCL") (class "Default")
      (node (ref "Cn36") (pin "4") (pinfunction "4_4") (pintype "passive"))
      (node (ref "Cn37") (pin "4") (pinfunction "4_4") (pintype "passive"))
      (node (ref "U7") (pin "12") (pinfunction "SCL_12") (pintype "passive"))
    )
    (net (code "38") (name "/SDA") (class "Default")
      (node (ref "Cn36") (pin "3") (pinfunction "3_3") (pintype "passive"))
      (node (ref "Cn37") (pin "3") (pinfunction "3_3") (pintype "passive"))
      (node (ref "U7") (pin "13") (pinfunction "SDA_13") (pintype "passive"))
    )
    (net (code "39") (name "GND") (class "Default")
      (node (ref "Cn36") (pin "1") (pinfunction "1_1") (pintype "passive"))
      (node (ref "Cn37") (pin "1") (pinfunction "1_1") (pintype "passive"))
      (node (ref "Cn39") (pin "1") (pinfunction "1_1") (pintype "passive"))
      (node (ref "Cn41") (pin "1") (pinfunction "1_1") (pintype "passive"))
      (node (ref "Cn42") (pin "1") (pinfunction "1_1") (pintype "passive"))
      (node (ref "Cn44") (pin "1") (pinfunction "1_1") (pintype "passive"))
      (node (ref "Cn46") (pin "2") (pinfunction "GND_2") (pintype "passive"))
      (node (ref "Cn46") (pin "3") (pinfunction "GND_3") (pintype "passive"))
      (node (ref "Cn56") (pin "1") (pinfunction "1_1") (pintype "passive"))
      (node (ref "Cn57") (pin "1") (pinfunction "1_1") (pintype "passive"))
      (node (ref "Cn58") (pin "1") (pinfunction "1_1") (pintype "passive"))
      (node (ref "Cn59") (pin "1") (pinfunction "1_1") (pintype "passive"))
      (node (ref "Cn60") (pin "1") (pinfunction "1_1") (pintype "passive"))
      (node (ref "Cn61") (pin "1") (pinfunction "1_1") (pintype "passive"))
      (node (ref "Cn62") (pin "1") (pinfunction "1_1") (pintype "passive"))
      (node (ref "Cn63") (pin "1") (pinfunction "1_1") (pintype "passive"))
      (node (ref "Cn64") (pin "1") (pinfunction "1_1") (pintype "passive"))
      (node (ref "Cn65") (pin "1") (pinfunction "1_1") (pintype "passive"))
      (node (ref "Cn66") (pin "1") (pinfunction "1_1") (pintype "passive"))
      (node (ref "Cn67") (pin "1") (pinfunction "1_1") (pintype "passive"))
      (node (ref "Cn68") (pin "1") (pinfunction "1_1") (pintype "passive"))
      (node (ref "Cn69") (pin "1") (pinfunction "1_1") (pintype "passive"))
      (node (ref "Cn70") (pin "1") (pinfunction "1_1") (pintype "passive"))
      (node (ref "Cn71") (pin "1") (pinfunction "1_1") (pintype "passive"))
      (node (ref "M10") (pin "1") (pinfunction "GND_1") (pintype "passive"))
      (node (ref "M11") (pin "1") (pinfunction "GND_1") (pintype "passive"))
      (node (ref "M8") (pin "1") (pinfunction "GND_1") (pintype "passive"))
      (node (ref "M9") (pin "1") (pinfunction "GND_1") (pintype "passive"))
      (node (ref "R105") (pin "1") (pinfunction "1_1") (pintype "passive"))
      (node (ref "R106") (pin "1") (pinfunction "1_1") (pintype "passive"))
      (node (ref "R107") (pin "1") (pinfunction "1_1") (pintype "passive"))
      (node (ref "TB11") (pin "2") (pinfunction "2_2") (pintype "passive"))
      (node (ref "TB8") (pin "2") (pinfunction "2_2") (pintype "passive"))
      (node (ref "U10") (pin "9") (pinfunction "GND_9") (pintype "passive"))
      (node (ref "U4") (pin "1") (pinfunction "ADJ/GND_1") (pintype "passive"))
      (node (ref "U6") (pin "9") (pinfunction "GND_9") (pintype "passive"))
      (node (ref "U7") (pin "10") (pinfunction "VSS_10") (pintype "passive"))
    )
    (net (code "40") (name "Net-(DZ1-K)") (class "Default")
      (node (ref "DZ1") (pin "1") (pinfunction "K_1") (pintype "passive"))
      (node (ref "R42") (pin "2") (pinfunction "2_2") (pintype "passive"))
      (node (ref "R43") (pin "2") (pinfunction "2_2") (pintype "passive"))
      (node (ref "R44") (pin "2") (pinfunction "2_2") (pintype "passive"))
      (node (ref "R45") (pin "2") (pinfunction "2_2") (pintype "passive"))
      (node (ref "R46") (pin "2") (pinfunction "2_2") (pintype "passive"))
      (node (ref "R65") (pin "2") (pinfunction "2_2") (pintype "passive"))
      (node (ref "R66") (pin "2") (pinfunction "2_2") (pintype "passive"))
      (node (ref "R67") (pin "2") (pinfunction "2_2") (pintype "passive"))
    )
    (net (code "41") (name "Net-(DZ2-K)") (class "Default")
      (node (ref "DZ2") (pin "1") (pinfunction "K_1") (pintype "passive"))
      (node (ref "R113") (pin "2") (pinfunction "2_2") (pintype "passive"))
      (node (ref "R114") (pin "2") (pinfunction "2_2") (pintype "passive"))
      (node (ref "R115") (pin "2") (pinfunction "2_2") (pintype "passive"))
      (node (ref "R116") (pin "2") (pinfunction "2_2") (pintype "passive"))
      (node (ref "R117") (pin "2") (pinfunction "2_2") (pintype "passive"))
      (node (ref "R118") (pin "2") (pinfunction "2_2") (pintype "passive"))
      (node (ref "R119") (pin "2") (pinfunction "2_2") (pintype "passive"))
      (node (ref "R124") (pin "2") (pinfunction "2_2") (pintype "passive"))
    )
    (net (code "42") (name "Net-(L5-A)") (class "Default")
      (node (ref "L5") (pin "2") (pinfunction "A_2") (pintype "passive"))
      (node (ref "R42") (pin "1") (pinfunction "1_1") (pintype "passive"))
    )
    (net (code "43") (name "Net-(L6-A)") (class "Default")
      (node (ref "L6") (pin "2") (pinfunction "A_2") (pintype "passive"))
      (node (ref "R43") (pin "1") (pinfunction "1_1") (pintype "passive"))
    )
    (net (code "44") (name "Net-(L7-A)") (class "Default")
      (node (ref "L7") (pin "2") (pinfunction "A_2") (pintype "passive"))
      (node (ref "R44") (pin "1") (pinfunction "1_1") (pintype "passive"))
    )
    (net (code "45") (name "Net-(L9-A)") (class "Default")
      (node (ref "L9") (pin "2") (pinfunction "A_2") (pintype "passive"))
      (node (ref "R45") (pin "1") (pinfunction "1_1") (pintype "passive"))
    )
    (net (code "46") (name "Net-(L16-A)") (class "Default")
      (node (ref "L16") (pin "2") (pinfunction "A_2") (pintype "passive"))
      (node (ref "R46") (pin "1") (pinfunction "1_1") (pintype "passive"))
    )
    (net (code "47") (name "Net-(L17-A)") (class "Default")
      (node (ref "L17") (pin "2") (pinfunction "A_2") (pintype "passive"))
      (node (ref "R65") (pin "1") (pinfunction "1_1") (pintype "passive"))
    )
    (net (code "48") (name "Net-(L18-A)") (class "Default")
      (node (ref "L18") (pin "2") (pinfunction "A_2") (pintype "passive"))
      (node (ref "R66") (pin "1") (pinfunction "1_1") (pintype "passive"))
    )
    (net (code "49") (name "Net-(L19-A)") (class "Default")
      (node (ref "L19") (pin "2") (pinfunction "A_2") (pintype "passive"))
      (node (ref "R67") (pin "1") (pinfunction "1_1") (pintype "passive"))
    )
    (net (code "50") (name "Net-(L24-A)") (class "Default")
      (node (ref "L24") (pin "2") (pinfunction "A_2") (pintype "passive"))
      (node (ref "R113") (pin "1") (pinfunction "1_1") (pintype "passive"))
    )
    (net (code "51") (name "Net-(L25-A)") (class "Default")
      (node (ref "L25") (pin "2") (pinfunction "A_2") (pintype "passive"))
      (node (ref "R114") (pin "1") (pinfunction "1_1") (pintype "passive"))
    )
    (net (code "52") (name "Net-(L26-A)") (class "Default")
      (node (ref "L26") (pin "2") (pinfunction "A_2") (pintype "passive"))
      (node (ref "R115") (pin "1") (pinfunction "1_1") (pintype "passive"))
    )
    (net (code "53") (name "Net-(L27-A)") (class "Default")
      (node (ref "L27") (pin "2") (pinfunction "A_2") (pintype "passive"))
      (node (ref "R116") (pin "1") (pinfunction "1_1") (pintype "passive"))
    )
    (net (code "54") (name "Net-(L28-A)") (class "Default")
      (node (ref "L28") (pin "2") (pinfunction "A_2") (pintype "passive"))
      (node (ref "R117") (pin "1") (pinfunction "1_1") (pintype "passive"))
    )
    (net (code "55") (name "Net-(L29-A)") (class "Default")
      (node (ref "L29") (pin "2") (pinfunction "A_2") (pintype "passive"))
      (node (ref "R118") (pin "1") (pinfunction "1_1") (pintype "passive"))
    )
    (net (code "56") (name "Net-(L30-A)") (class "Default")
      (node (ref "L30") (pin "2") (pinfunction "A_2") (pintype "passive"))
      (node (ref "R119") (pin "1") (pinfunction "1_1") (pintype "passive"))
    )
    (net (code "57") (name "Net-(L31-A)") (class "Default")
      (node (ref "L31") (pin "2") (pinfunction "A_2") (pintype "passive"))
      (node (ref "R124") (pin "1") (pinfunction "1_1") (pintype "passive"))
    )
    (net (code "58") (name "Vin") (class "Default")
      (node (ref "Cn36") (pin "2") (pinfunction "2_2") (pintype "passive"))
      (node (ref "Cn37") (pin "2") (pinfunction "2_2") (pintype "passive"))
      (node (ref "Cn56") (pin "4") (pinfunction "4_4") (pintype "passive"))
      (node (ref "Cn57") (pin "4") (pinfunction "4_4") (pintype "passive"))
      (node (ref "Cn58") (pin "4") (pinfunction "4_4") (pintype "passive"))
      (node (ref "Cn59") (pin "4") (pinfunction "4_4") (pintype "passive"))
      (node (ref "Cn60") (pin "4") (pinfunction "4_4") (pintype "passive"))
      (node (ref "Cn61") (pin "4") (pinfunction "4_4") (pintype "passive"))
      (node (ref "Cn62") (pin "4") (pinfunction "4_4") (pintype "passive"))
      (node (ref "Cn63") (pin "4") (pinfunction "4_4") (pintype "passive"))
      (node (ref "Cn64") (pin "4") (pinfunction "4_4") (pintype "passive"))
      (node (ref "Cn65") (pin "4") (pinfunction "4_4") (pintype "passive"))
      (node (ref "Cn66") (pin "4") (pinfunction "4_4") (pintype "passive"))
      (node (ref "Cn67") (pin "4") (pinfunction "4_4") (pintype "passive"))
      (node (ref "Cn68") (pin "4") (pinfunction "4_4") (pintype "passive"))
      (node (ref "Cn69") (pin "4") (pinfunction "4_4") (pintype "passive"))
      (node (ref "Cn70") (pin "4") (pinfunction "4_4") (pintype "passive"))
      (node (ref "Cn71") (pin "4") (pinfunction "4_4") (pintype "passive"))
      (node (ref "D2") (pin "1") (pinfunction "1_1") (pintype "passive"))
      (node (ref "D2") (pin "2") (pinfunction "2_2") (pintype "passive"))
      (node (ref "D2") (pin "3") (pinfunction "3_3") (pintype "passive"))
      (node (ref "DZ1") (pin "2") (pinfunction "A_2") (pintype "passive"))
      (node (ref "DZ2") (pin "2") (pinfunction "A_2") (pintype "passive"))
      (node (ref "M10") (pin "2") (pinfunction "2.5~5.5V_2") (pintype "passive"))
      (node (ref "M11") (pin "2") (pinfunction "2.5~5.5V_2") (pintype "passive"))
      (node (ref "M8") (pin "2") (pinfunction "2.5~5.5V_2") (pintype "passive"))
      (node (ref "M9") (pin "2") (pinfunction "2.5~5.5V_2") (pintype "passive"))
      (node (ref "U4") (pin "2") (pinfunction "OUT_2") (pintype "passive"))
      (node (ref "U7") (pin "18") (pinfunction "~{RESET}_18") (pintype "passive"))
      (node (ref "U7") (pin "9") (pinfunction "VDD_9") (pintype "passive"))
    )
    (net (code "59") (name "unconnected-(M8-VT-Pad7)") (class "Default")
      (node (ref "M8") (pin "7") (pinfunction "VT_7") (pintype "passive"))
    )
    (net (code "60") (name "unconnected-(M9-VT-Pad7)") (class "Default")
      (node (ref "M9") (pin "7") (pinfunction "VT_7") (pintype "passive"))
    )
    (net (code "61") (name "unconnected-(M10-VT-Pad7)") (class "Default")
      (node (ref "M10") (pin "7") (pinfunction "VT_7") (pintype "passive"))
    )
    (net (code "62") (name "unconnected-(M11-VT-Pad7)") (class "Default")
      (node (ref "M11") (pin "7") (pinfunction "VT_7") (pintype "passive"))
    )
    (net (code "63") (name "unconnected-(U7-INTA-Pad20)") (class "Default")
      (node (ref "U7") (pin "20") (pinfunction "INTA_20") (pintype "passive"))
    )
    (net (code "64") (name "unconnected-(U7-INTB-Pad19)") (class "Default")
      (node (ref "U7") (pin "19") (pinfunction "INTB_19") (pintype "passive"))
    )
    (net (code "65") (name "unconnected-(U7-NC_1-Pad11)") (class "Default")
      (node (ref "U7") (pin "11") (pinfunction "NC_1_11") (pintype "passive"))
    )
    (net (code "66") (name "unconnected-(U7-NC_2-Pad14)") (class "Default")
      (node (ref "U7") (pin "14") (pinfunction "NC_2_14") (pintype "passive"))
    )
  )
)
